# Sapflux-Basic_AltC.net
KiCad netlist of a schematic drawn in EAGLE
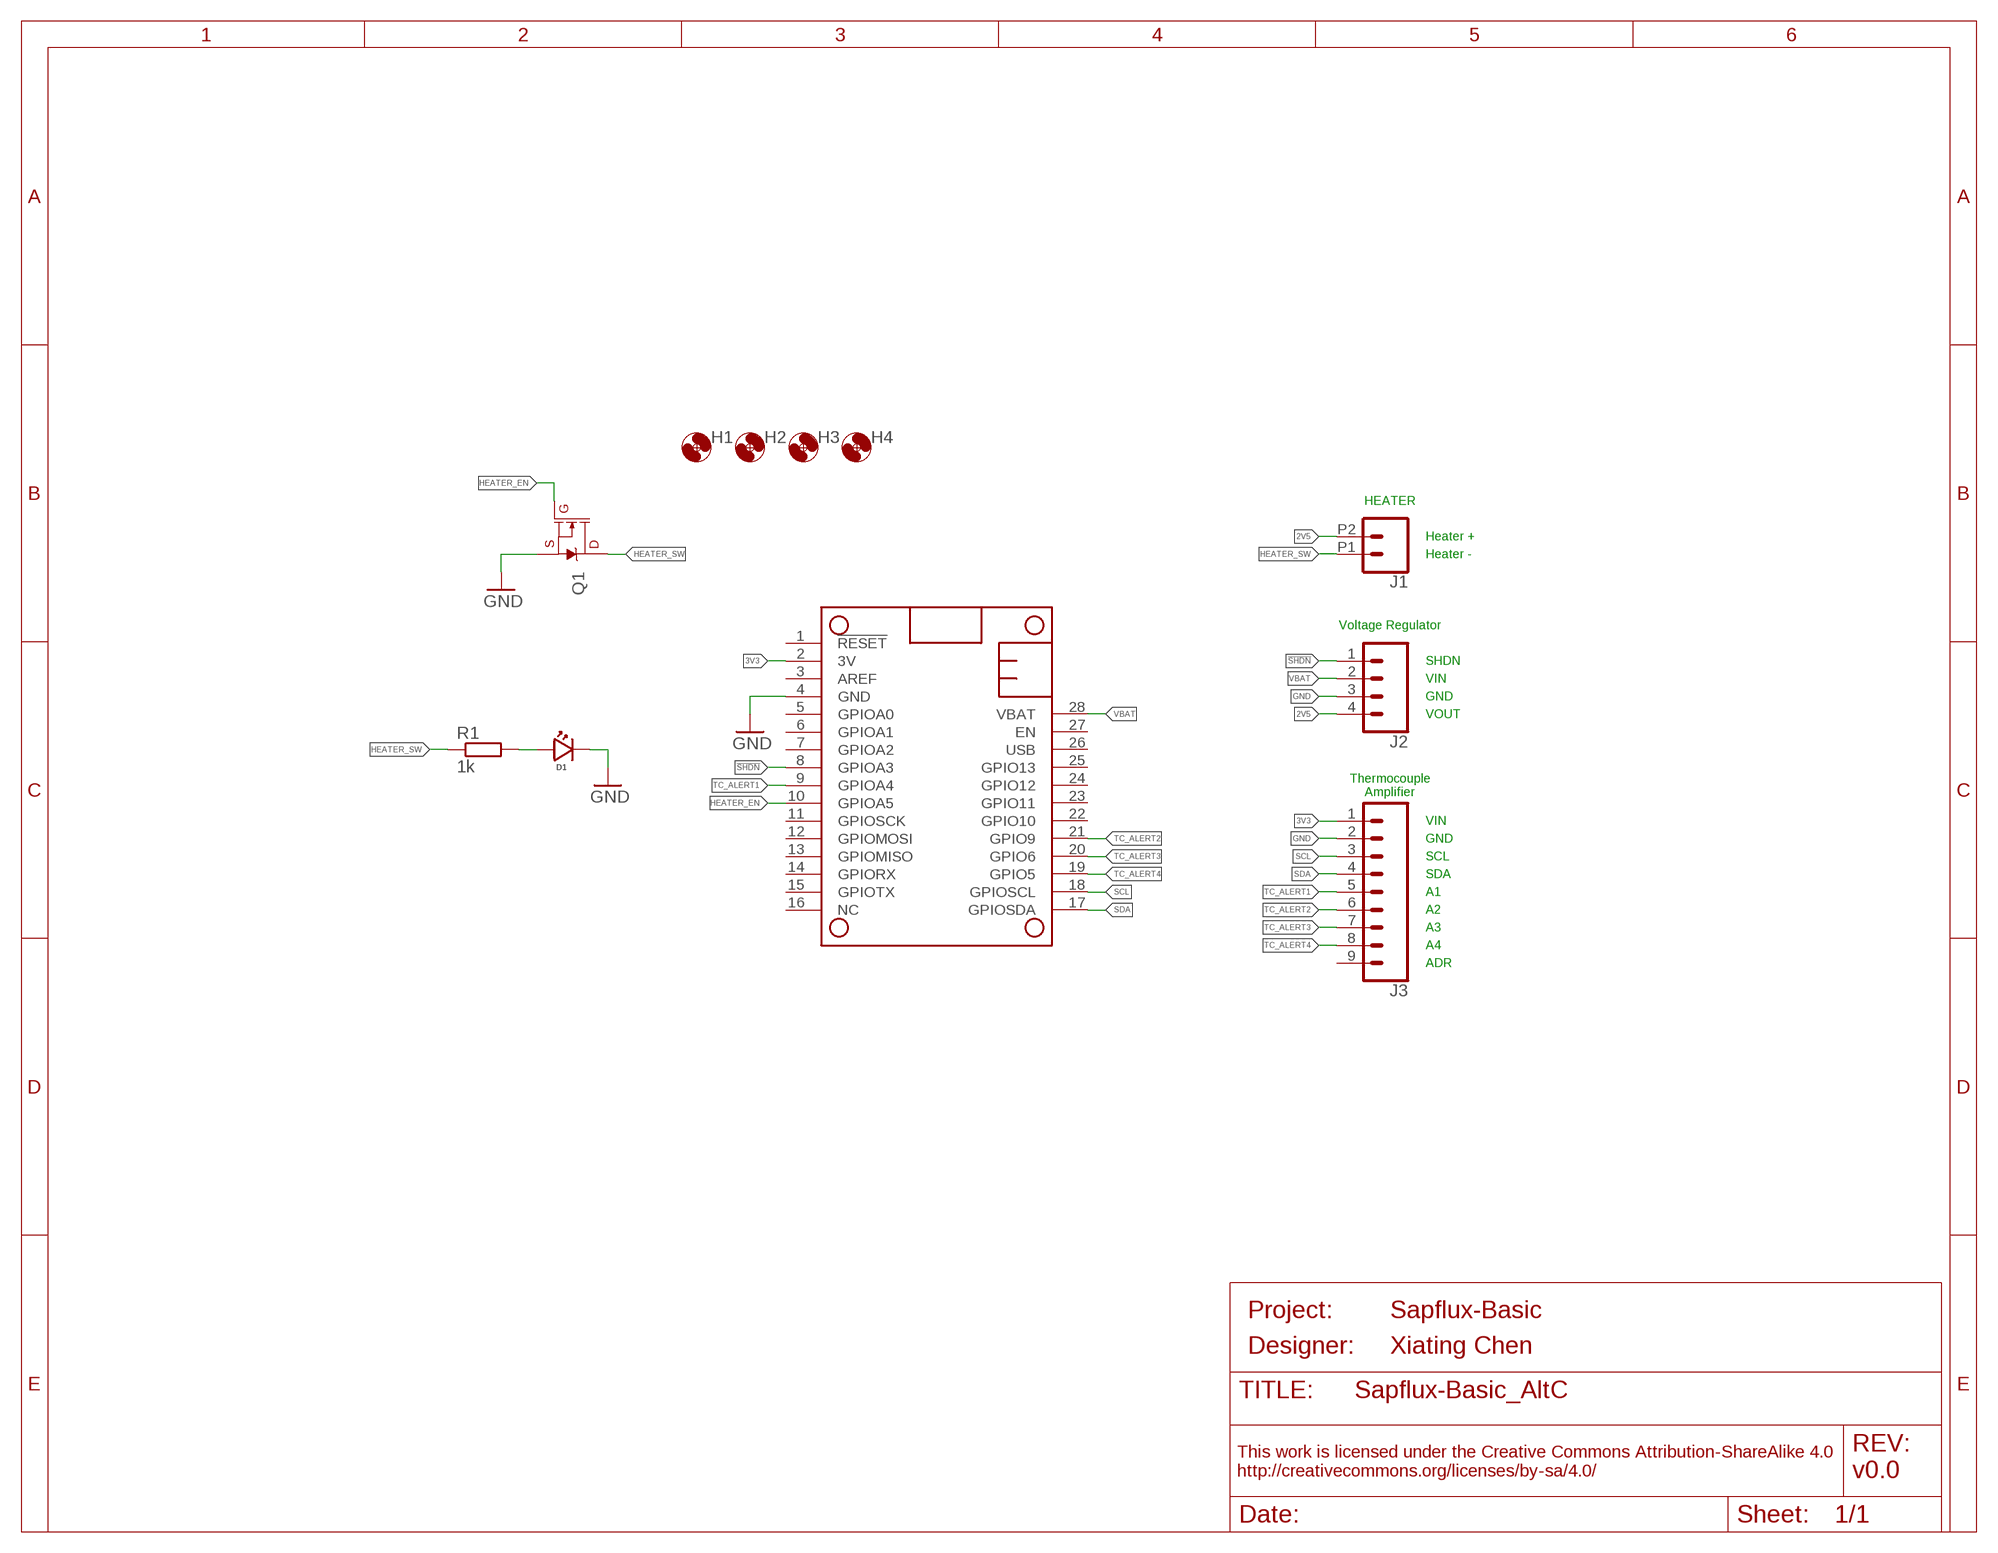
[diagram p0: schematic, sheet 1]

(export (version "E")
  (design (tool "Eeschema 10.0.6"))
  (components
    (comp (ref "D1")
      (value "LED3MM")
      (footprint "eagle-import:LED_3MM")
      (libsource (lib "eagle-import") (part "LED3MM"))
    )
    (comp (ref "H1")
      (value "MOUNTING_HOLE4_NP")
      (footprint "eagle-import:4_40")
      (fields (field (name "MPN") "DNP"))
      (libsource (lib "eagle-import") (part "MOUNTING_HOLE4_NP"))
    )
    (comp (ref "H2")
      (value "MOUNTING_HOLE4_NP")
      (footprint "eagle-import:4_40")
      (fields (field (name "MPN") "DNP"))
      (libsource (lib "eagle-import") (part "MOUNTING_HOLE4_NP"))
    )
    (comp (ref "H3")
      (value "MOUNTING_HOLE4_NP")
      (footprint "eagle-import:4_40")
      (fields (field (name "MPN") "DNP"))
      (libsource (lib "eagle-import") (part "MOUNTING_HOLE4_NP"))
    )
    (comp (ref "H4")
      (value "MOUNTING_HOLE4_NP")
      (footprint "eagle-import:4_40")
      (fields (field (name "MPN") "DNP"))
      (libsource (lib "eagle-import") (part "MOUNTING_HOLE4_NP"))
    )
    (comp (ref "J1")
      (value "CONN_2")
      (footprint "eagle-import:1X02_2.54_SCREWTERM_ROUND")
      (fields (field (name "MF") "OnShore") (field (name "MPN") "OSTVN02A150"))
      (libsource (lib "eagle-import") (part "CONN_022.54_SCREW_ROUND"))
    )
    (comp (ref "J2")
      (value "CONN_42.54")
      (footprint "eagle-import:1X04")
      (fields (field (name "MF") "Adam Tech") (field (name "MPN") "PH1-04-UA"))
      (libsource (lib "eagle-import") (part "CONN_42.54"))
    )
    (comp (ref "J3")
      (value "CONN_9")
      (footprint "eagle-import:1X09")
      (fields (field (name "MF") "Adam Tech") (field (name "MPN") "PH1-09-UA"))
      (libsource (lib "eagle-import") (part "CONN_9"))
    )
    (comp (ref "MS1")
      (value "FEATHERWINGLAYOUT")
      (footprint "eagle-import:FEATHERWING_MIN")
      (libsource (lib "eagle-import") (part "FEATHERWINGLAYOUT"))
    )
    (comp (ref "Q1")
      (value "60V/32A/35mΩ")
      (footprint "eagle-import:TO220V")
      (fields (field (name "MF") "Infineon") (field (name "MPN") "IRLB8721PBF"))
      (libsource (lib "eagle-import") (part "MOSFET-NCH-FQP30N06L"))
    )
    (comp (ref "R1")
      (value "1k")
      (footprint "eagle-import:0204_7")
      (libsource (lib "eagle-import") (part "R-EU_0204/7"))
    )
  )
  (nets
    (net (code "1") (name "/USB") (class "Default")
      (node (ref "MS1") (pin "26") (pinfunction "USB_26") (pintype "power_in"))
    )
    (net (code "2") (name "/~{SHDN}") (class "Default")
      (node (ref "J2") (pin "1") (pinfunction "1_1") (pintype "passive"))
      (node (ref "MS1") (pin "8") (pinfunction "GPIOA3_8") (pintype "bidirectional"))
    )
    (net (code "3") (name "2V5") (class "Default")
      (node (ref "J1") (pin "P2") (pinfunction "2_P2") (pintype "passive"))
      (node (ref "J2") (pin "4") (pinfunction "4_4") (pintype "passive"))
    )
    (net (code "4") (name "3V3") (class "Default")
      (node (ref "J3") (pin "1") (pinfunction "1_1") (pintype "passive"))
      (node (ref "MS1") (pin "2") (pinfunction "3V_2") (pintype "power_in"))
    )
    (net (code "5") (name "GND") (class "Default")
      (node (ref "D1") (pin "2") (pinfunction "CATHODE_2") (pintype "power_in"))
      (node (ref "J2") (pin "3") (pinfunction "3_3") (pintype "passive"))
      (node (ref "J3") (pin "2") (pinfunction "2_2") (pintype "passive"))
      (node (ref "MS1") (pin "4") (pinfunction "GND_4") (pintype "power_in"))
      (node (ref "Q1") (pin "3") (pinfunction "S_3") (pintype "bidirectional"))
    )
    (net (code "6") (name "HEATER_EN") (class "Default")
      (node (ref "MS1") (pin "10") (pinfunction "GPIOA5_10") (pintype "bidirectional"))
      (node (ref "Q1") (pin "1") (pinfunction "G_1") (pintype "bidirectional"))
    )
    (net (code "7") (name "HEATER_SW") (class "Default")
      (node (ref "J1") (pin "P1") (pinfunction "1_P1") (pintype "passive"))
      (node (ref "Q1") (pin "2") (pinfunction "D_2") (pintype "bidirectional"))
      (node (ref "R1") (pin "1") (pinfunction "1_1") (pintype "passive"))
    )
    (net (code "8") (name "Net-(D1-ANODE)") (class "Default")
      (node (ref "D1") (pin "1") (pinfunction "ANODE_1") (pintype "power_in"))
      (node (ref "R1") (pin "2") (pinfunction "2_2") (pintype "passive"))
    )
    (net (code "9") (name "SCL") (class "Default")
      (node (ref "J3") (pin "3") (pinfunction "3_3") (pintype "passive"))
      (node (ref "MS1") (pin "18") (pinfunction "GPIOSCL_18") (pintype "bidirectional"))
    )
    (net (code "10") (name "SDA") (class "Default")
      (node (ref "J3") (pin "4") (pinfunction "4_4") (pintype "passive"))
      (node (ref "MS1") (pin "17") (pinfunction "GPIOSDA_17") (pintype "bidirectional"))
    )
    (net (code "11") (name "TC_ALERT1") (class "Default")
      (node (ref "J3") (pin "5") (pinfunction "5_5") (pintype "passive"))
      (node (ref "MS1") (pin "9") (pinfunction "GPIOA4_9") (pintype "bidirectional"))
    )
    (net (code "12") (name "TC_ALERT2") (class "Default")
      (node (ref "J3") (pin "6") (pinfunction "6_6") (pintype "passive"))
      (node (ref "MS1") (pin "21") (pinfunction "GPIO9_21") (pintype "bidirectional"))
    )
    (net (code "13") (name "TC_ALERT3") (class "Default")
      (node (ref "J3") (pin "7") (pinfunction "7_7") (pintype "passive"))
      (node (ref "MS1") (pin "20") (pinfunction "GPIO6_20") (pintype "bidirectional"))
    )
    (net (code "14") (name "TC_ALERT4") (class "Default")
      (node (ref "J3") (pin "8") (pinfunction "8_8") (pintype "passive"))
      (node (ref "MS1") (pin "19") (pinfunction "GPIO5_19") (pintype "bidirectional"))
    )
    (net (code "15") (name "VBAT") (class "Default")
      (node (ref "J2") (pin "2") (pinfunction "2_2") (pintype "passive"))
      (node (ref "MS1") (pin "28") (pinfunction "VBAT_28") (pintype "power_in"))
    )
    (net (code "16") (name "unconnected-(J3-Pad9)") (class "Default")
      (node (ref "J3") (pin "9") (pinfunction "9_9") (pintype "passive"))
    )
    (net (code "17") (name "unconnected-(MS1-AREF-Pad3)") (class "Default")
      (node (ref "MS1") (pin "3") (pinfunction "AREF_3") (pintype "passive"))
    )
    (net (code "18") (name "unconnected-(MS1-EN-Pad27)") (class "Default")
      (node (ref "MS1") (pin "27") (pinfunction "EN_27") (pintype "passive"))
    )
    (net (code "19") (name "unconnected-(MS1-GPIO10-Pad22)") (class "Default")
      (node (ref "MS1") (pin "22") (pinfunction "GPIO10_22") (pintype "bidirectional"))
    )
    (net (code "20") (name "unconnected-(MS1-GPIO11-Pad23)") (class "Default")
      (node (ref "MS1") (pin "23") (pinfunction "GPIO11_23") (pintype "bidirectional"))
    )
    (net (code "21") (name "unconnected-(MS1-GPIO12-Pad24)") (class "Default")
      (node (ref "MS1") (pin "24") (pinfunction "GPIO12_24") (pintype "bidirectional"))
    )
    (net (code "22") (name "unconnected-(MS1-GPIO13-Pad25)") (class "Default")
      (node (ref "MS1") (pin "25") (pinfunction "GPIO13_25") (pintype "bidirectional"))
    )
    (net (code "23") (name "unconnected-(MS1-GPIOA0-Pad5)") (class "Default")
      (node (ref "MS1") (pin "5") (pinfunction "GPIOA0_5") (pintype "bidirectional"))
    )
    (net (code "24") (name "unconnected-(MS1-GPIOA1-Pad6)") (class "Default")
      (node (ref "MS1") (pin "6") (pinfunction "GPIOA1_6") (pintype "bidirectional"))
    )
    (net (code "25") (name "unconnected-(MS1-GPIOA2-Pad7)") (class "Default")
      (node (ref "MS1") (pin "7") (pinfunction "GPIOA2_7") (pintype "bidirectional"))
    )
    (net (code "26") (name "unconnected-(MS1-GPIOMISO-Pad13)") (class "Default")
      (node (ref "MS1") (pin "13") (pinfunction "GPIOMISO_13") (pintype "bidirectional"))
    )
    (net (code "27") (name "unconnected-(MS1-GPIOMOSI-Pad12)") (class "Default")
      (node (ref "MS1") (pin "12") (pinfunction "GPIOMOSI_12") (pintype "bidirectional"))
    )
    (net (code "28") (name "unconnected-(MS1-GPIORX-Pad14)") (class "Default")
      (node (ref "MS1") (pin "14") (pinfunction "GPIORX_14") (pintype "bidirectional"))
    )
    (net (code "29") (name "unconnected-(MS1-GPIOSCK-Pad11)") (class "Default")
      (node (ref "MS1") (pin "11") (pinfunction "GPIOSCK_11") (pintype "bidirectional"))
    )
    (net (code "30") (name "unconnected-(MS1-GPIOTX-Pad15)") (class "Default")
      (node (ref "MS1") (pin "15") (pinfunction "GPIOTX_15") (pintype "bidirectional"))
    )
    (net (code "31") (name "unconnected-(MS1-NC-Pad16)") (class "Default")
      (node (ref "MS1") (pin "16") (pinfunction "NC_16") (pintype "passive"))
    )
    (net (code "32") (name "unconnected-(MS1-~{RESET}-Pad1)") (class "Default")
      (node (ref "MS1") (pin "1") (pinfunction "~{RESET}_1") (pintype "input"))
    )
  )
)
